# Lepton.net
KiCad netlist of a schematic drawn in EAGLE
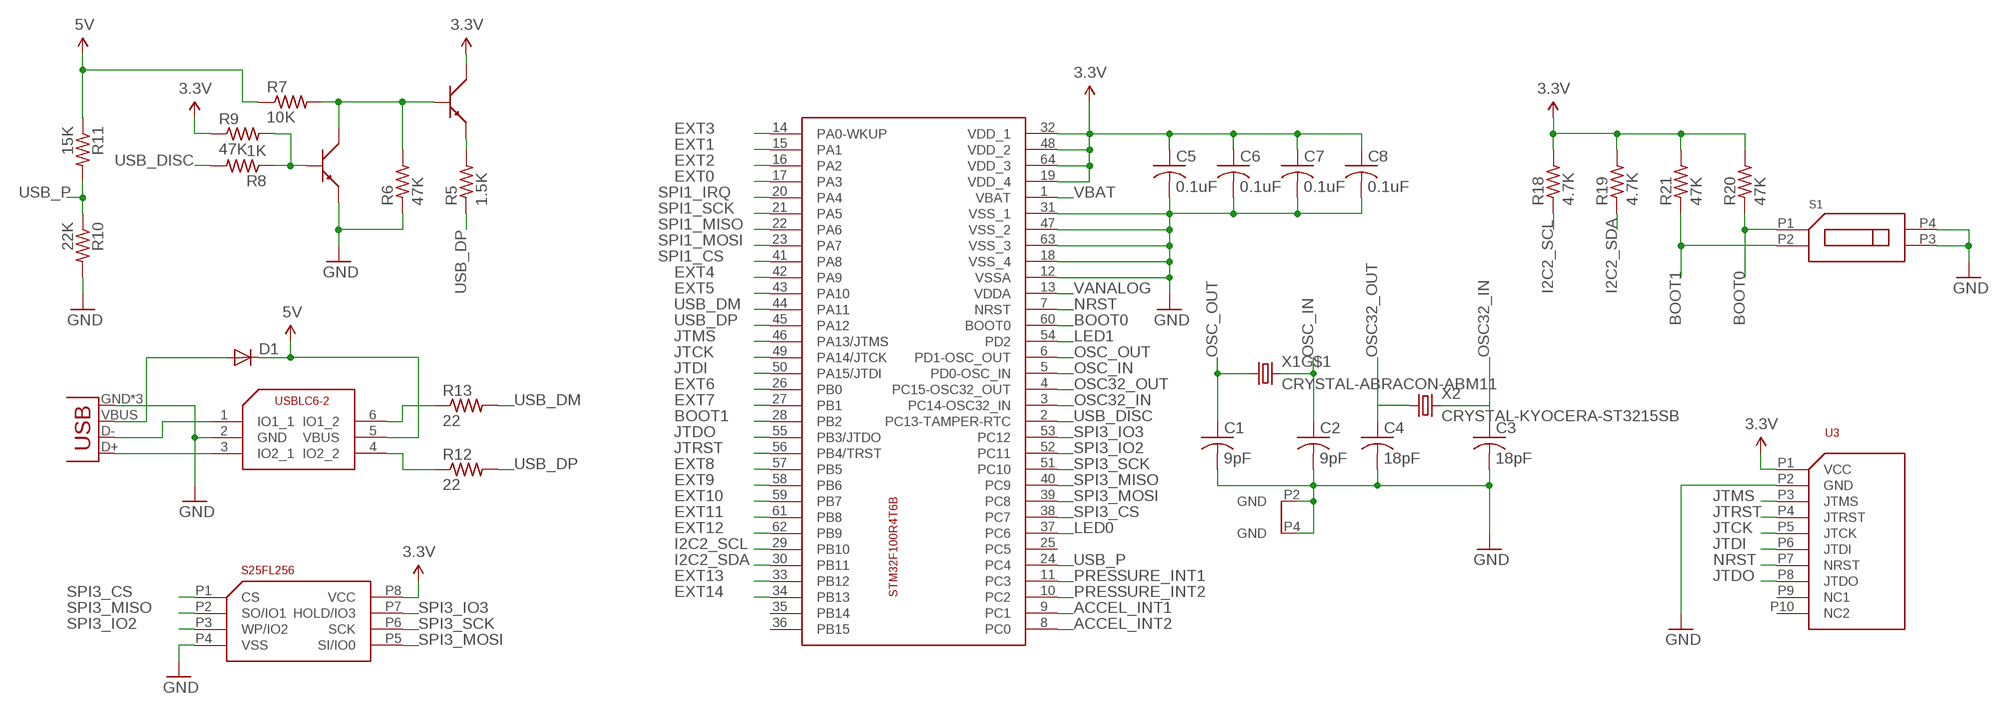
[diagram p0: schematic, sheet 1]
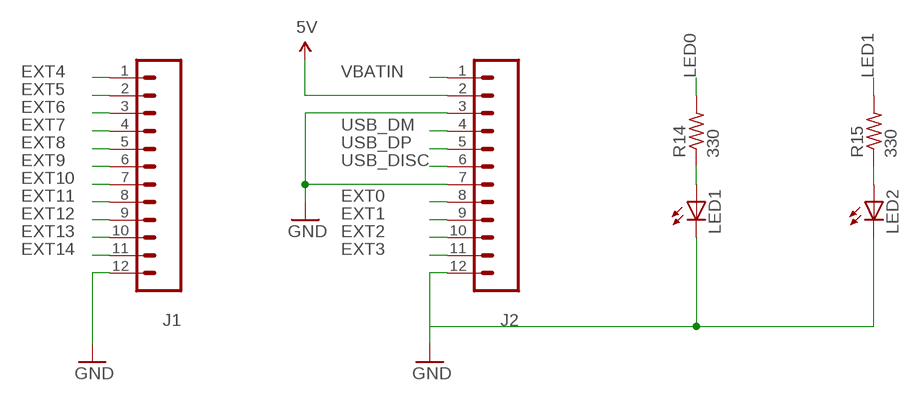
[diagram p1: schematic, sheet 2]
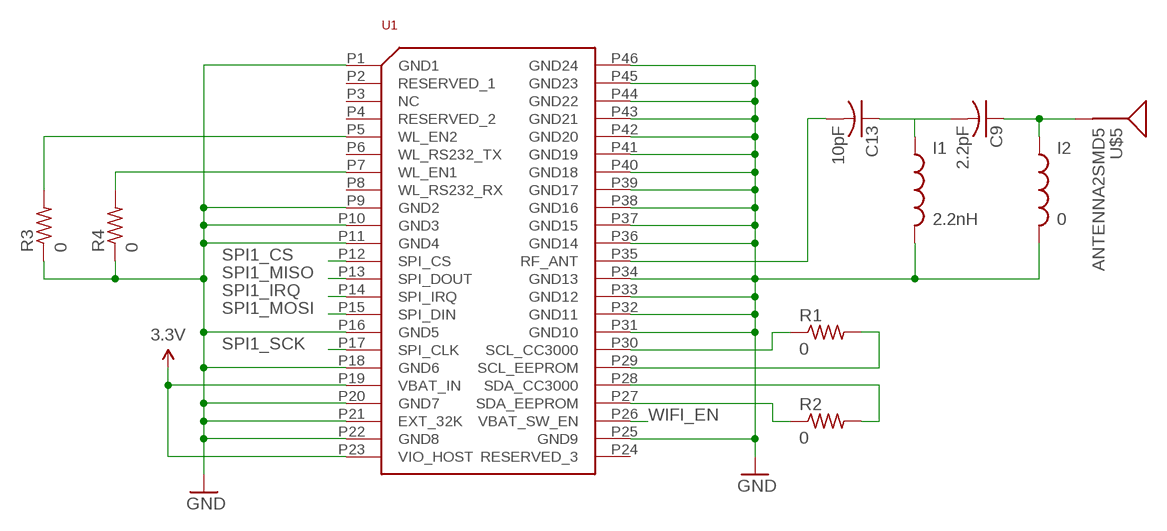
[diagram p2: schematic, sheet 3]
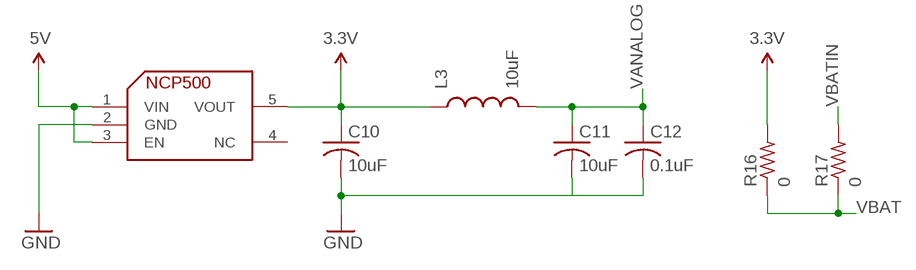
[diagram p3: schematic, sheet 4]
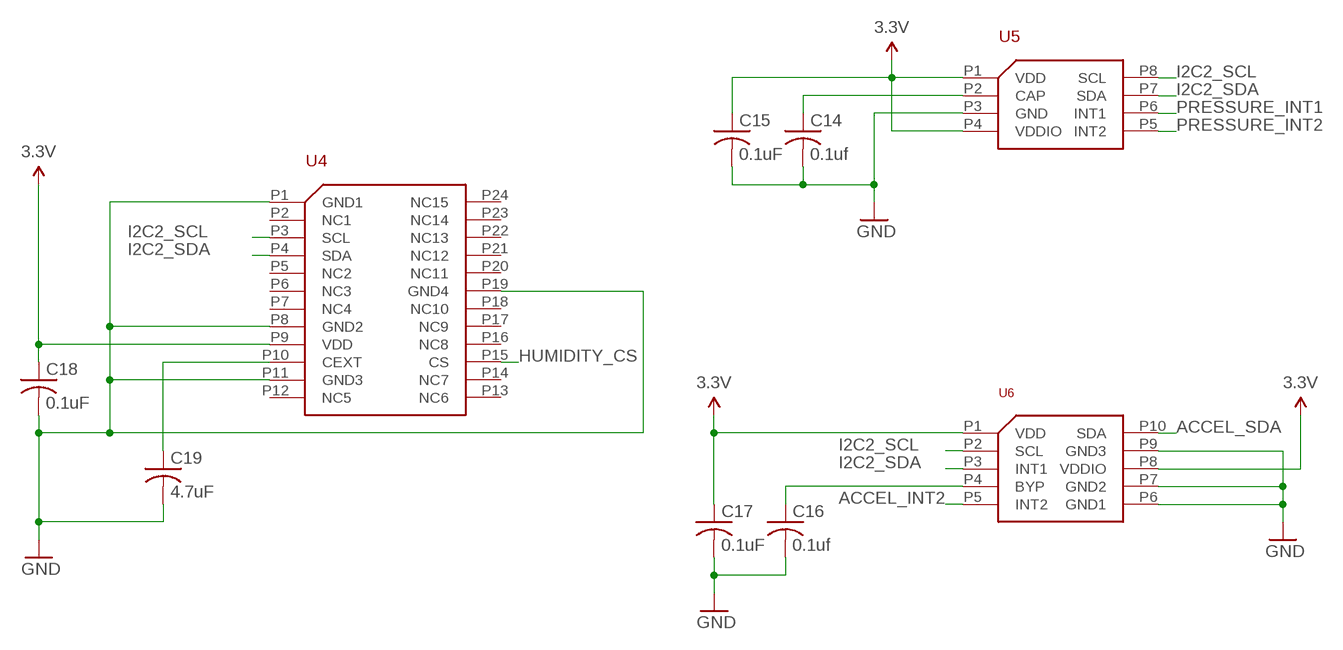
[diagram p4: schematic, sheet 5]

(export (version "E")
  (design (tool "Eeschema 10.0.6"))
  (components
    (comp (ref "C10")
      (value "10uF")
      (footprint "eagle-import:C0603")
      (libsource (lib "eagle-import") (part "C-USC0603"))
    )
    (comp (ref "C11")
      (value "10uF")
      (footprint "eagle-import:C0603")
      (libsource (lib "eagle-import") (part "C-USC0603"))
    )
    (comp (ref "C12")
      (value "0.1uF")
      (footprint "eagle-import:C0201")
      (libsource (lib "eagle-import") (part "C-USC0201"))
    )
    (comp (ref "L3")
      (value "10uF")
      (footprint "eagle-import:0603")
      (libsource (lib "eagle-import") (part "INDUCTOR0603"))
    )
    (comp (ref "R16")
      (value "0")
      (footprint "eagle-import:R0402")
      (libsource (lib "eagle-import") (part "R-US_R0402"))
    )
    (comp (ref "R17")
      (value "0")
      (footprint "eagle-import:R0402")
      (libsource (lib "eagle-import") (part "R-US_R0402"))
    )
    (comp (ref "U$7")
      (value "NCP500")
      (footprint "eagle-import:SOT23-5L")
      (libsource (lib "eagle-import") (part "NCP500"))
    )
    (comp (ref "C9")
      (value "2.2pF")
      (footprint "eagle-import:C0201")
      (libsource (lib "eagle-import") (part "C-USC0201"))
    )
    (comp (ref "C13")
      (value "10pF")
      (footprint "eagle-import:C0201")
      (libsource (lib "eagle-import") (part "C-USC0201"))
    )
    (comp (ref "I1")
      (value "2.2nH")
      (footprint "eagle-import:C0402")
      (libsource (lib "eagle-import") (part "INDUCTOR0402"))
    )
    (comp (ref "I2")
      (value "0")
      (footprint "eagle-import:C0402")
      (libsource (lib "eagle-import") (part "INDUCTOR0402"))
    )
    (comp (ref "R1")
      (value "0")
      (footprint "eagle-import:R0201")
      (libsource (lib "eagle-import") (part "R-US_R0201"))
    )
    (comp (ref "R2")
      (value "0")
      (footprint "eagle-import:R0201")
      (libsource (lib "eagle-import") (part "R-US_R0201"))
    )
    (comp (ref "R3")
      (value "0")
      (footprint "eagle-import:R0201")
      (libsource (lib "eagle-import") (part "R-US_R0201"))
    )
    (comp (ref "R4")
      (value "0")
      (footprint "eagle-import:R0201")
      (libsource (lib "eagle-import") (part "R-US_R0201"))
    )
    (comp (ref "U$5")
      (value "ANTENNA2SMD5")
      (footprint "eagle-import:ANTENNA-CHIP5")
      (libsource (lib "eagle-import") (part "ANTENNA2SMD5"))
    )
    (comp (ref "U1")
      (value "CC3000")
      (footprint "eagle-import:CC3000")
      (libsource (lib "eagle-import") (part "CC3000"))
    )
    (comp (ref "J1")
      (value "M12")
      (footprint "eagle-import:1X12")
      (libsource (lib "eagle-import") (part "M12"))
    )
    (comp (ref "J2")
      (value "M12")
      (footprint "eagle-import:1X12")
      (libsource (lib "eagle-import") (part "M12"))
    )
    (comp (ref "LED1")
      (value "LED0603")
      (footprint "eagle-import:LED-0603")
      (libsource (lib "eagle-import") (part "LED0603"))
    )
    (comp (ref "LED2")
      (value "LED0603")
      (footprint "eagle-import:LED-0603")
      (libsource (lib "eagle-import") (part "LED0603"))
    )
    (comp (ref "R14")
      (value "330")
      (footprint "eagle-import:R0201")
      (libsource (lib "eagle-import") (part "R-US_R0201"))
    )
    (comp (ref "R15")
      (value "330")
      (footprint "eagle-import:R0201")
      (libsource (lib "eagle-import") (part "R-US_R0201"))
    )
    (comp (ref "C14")
      (value "0.1uf")
      (footprint "eagle-import:C0201")
      (libsource (lib "eagle-import") (part "C-USC0201"))
    )
    (comp (ref "C15")
      (value "0.1uF")
      (footprint "eagle-import:C0201")
      (libsource (lib "eagle-import") (part "C-USC0201"))
    )
    (comp (ref "C16")
      (value "0.1uf")
      (footprint "eagle-import:C0201")
      (libsource (lib "eagle-import") (part "C-USC0201"))
    )
    (comp (ref "C17")
      (value "0.1uF")
      (footprint "eagle-import:C0201")
      (libsource (lib "eagle-import") (part "C-USC0201"))
    )
    (comp (ref "C18")
      (value "0.1uF")
      (footprint "eagle-import:C0201")
      (libsource (lib "eagle-import") (part "C-USC0201"))
    )
    (comp (ref "C19")
      (value "4.7uF")
      (footprint "eagle-import:C0402")
      (libsource (lib "eagle-import") (part "C-USC0402"))
    )
    (comp (ref "U4")
      (value "SILICONLABS-HUMIDITY-SI7005")
      (footprint "eagle-import:SILICONLABS-TQFN-24")
      (libsource (lib "eagle-import") (part "SILICONLABS-HUMIDITY-SI7005"))
    )
    (comp (ref "U5")
      (value "FREESCALE-PRESSURE-MPL3115A2")
      (footprint "eagle-import:UQFN-8L")
      (libsource (lib "eagle-import") (part "FREESCALE-PRESSURE-MPL3115A2"))
    )
    (comp (ref "U6")
      (value "MMA8653FC")
      (footprint "eagle-import:DFN-2X2-10")
      (libsource (lib "eagle-import") (part "MMA8653FC"))
    )
    (comp (ref "C1")
      (value "9pF")
      (footprint "eagle-import:C0201")
      (libsource (lib "eagle-import") (part "C-USC0201"))
    )
    (comp (ref "C2")
      (value "9pF")
      (footprint "eagle-import:C0201")
      (libsource (lib "eagle-import") (part "C-USC0201"))
    )
    (comp (ref "C3")
      (value "18pF")
      (footprint "eagle-import:C0201")
      (libsource (lib "eagle-import") (part "C-USC0201"))
    )
    (comp (ref "C4")
      (value "18pF")
      (footprint "eagle-import:C0201")
      (libsource (lib "eagle-import") (part "C-USC0201"))
    )
    (comp (ref "C5")
      (value "0.1uF")
      (footprint "eagle-import:C0201")
      (libsource (lib "eagle-import") (part "C-USC0201"))
    )
    (comp (ref "C6")
      (value "0.1uF")
      (footprint "eagle-import:C0201")
      (libsource (lib "eagle-import") (part "C-USC0201"))
    )
    (comp (ref "C7")
      (value "0.1uF")
      (footprint "eagle-import:C0201")
      (libsource (lib "eagle-import") (part "C-USC0201"))
    )
    (comp (ref "C8")
      (value "0.1uF")
      (footprint "eagle-import:C0201")
      (libsource (lib "eagle-import") (part "C-USC0201"))
    )
    (comp (ref "D1")
      (value "DIODE-MINIMELF")
      (footprint "eagle-import:MINIMELF")
      (libsource (lib "eagle-import") (part "DIODE-MINIMELF"))
    )
    (comp (ref "JP1")
      (value "USB-MICROB")
      (footprint "eagle-import:USB-MICROB")
      (libsource (lib "eagle-import") (part "USB-MICROB"))
    )
    (comp (ref "R5")
      (value "1.5K")
      (footprint "eagle-import:R0402")
      (libsource (lib "eagle-import") (part "R-US_R0402"))
    )
    (comp (ref "R6")
      (value "47K")
      (footprint "eagle-import:R0402")
      (libsource (lib "eagle-import") (part "R-US_R0402"))
    )
    (comp (ref "R7")
      (value "10K")
      (footprint "eagle-import:R0201")
      (libsource (lib "eagle-import") (part "R-US_R0201"))
    )
    (comp (ref "R8")
      (value "1K")
      (footprint "eagle-import:R0201")
      (libsource (lib "eagle-import") (part "R-US_R0201"))
    )
    (comp (ref "R9")
      (value "47K")
      (footprint "eagle-import:R0201")
      (libsource (lib "eagle-import") (part "R-US_R0201"))
    )
    (comp (ref "R10")
      (value "22K")
      (footprint "eagle-import:R0201")
      (libsource (lib "eagle-import") (part "R-US_R0201"))
    )
    (comp (ref "R11")
      (value "15K")
      (footprint "eagle-import:R0201")
      (libsource (lib "eagle-import") (part "R-US_R0201"))
    )
    (comp (ref "R12")
      (value "22")
      (footprint "eagle-import:R0201")
      (libsource (lib "eagle-import") (part "R-US_R0201"))
    )
    (comp (ref "R13")
      (value "22")
      (footprint "eagle-import:R0201")
      (libsource (lib "eagle-import") (part "R-US_R0201"))
    )
    (comp (ref "R18")
      (value "4.7K")
      (footprint "eagle-import:R0201")
      (libsource (lib "eagle-import") (part "R-US_R0201"))
    )
    (comp (ref "R19")
      (value "4.7K")
      (footprint "eagle-import:R0201")
      (libsource (lib "eagle-import") (part "R-US_R0201"))
    )
    (comp (ref "R20")
      (value "47K")
      (footprint "eagle-import:R0201")
      (libsource (lib "eagle-import") (part "R-US_R0201"))
    )
    (comp (ref "R21")
      (value "47K")
      (footprint "eagle-import:R0201")
      (libsource (lib "eagle-import") (part "R-US_R0201"))
    )
    (comp (ref "S1")
      (value "SWITCH-DIP-GDH-02")
      (footprint "eagle-import:SWITCH-DIP-GDH-02")
      (libsource (lib "eagle-import") (part "SWITCH-DIP-GDH-02"))
    )
    (comp (ref "U$1")
      (value "SPANSION-S25FL256")
      (footprint "eagle-import:SPANSION-WSON-8")
      (libsource (lib "eagle-import") (part "SPANSION-S25FL256"))
    )
    (comp (ref "U$2")
      (value "BIPOLAR-PMBT6428")
      (footprint "eagle-import:DUBLIB_SOT23")
      (libsource (lib "eagle-import") (part "BIPOLAR-PMBT6428"))
    )
    (comp (ref "U$3")
      (value "BIPOLAR-PMBT6428")
      (footprint "eagle-import:DUBLIB_SOT23")
      (libsource (lib "eagle-import") (part "BIPOLAR-PMBT6428"))
    )
    (comp (ref "U$4")
      (value "USBLC6-2")
      (footprint "eagle-import:SOT23-6L")
      (libsource (lib "eagle-import") (part "USBLC6-2"))
    )
    (comp (ref "U2")
      (value "STM32F100R4T6B")
      (footprint "eagle-import:S-PQFP64-G64")
      (libsource (lib "eagle-import") (part "STM32F100R4T6B"))
    )
    (comp (ref "U3")
      (value "STM32-JTAG-FFC")
      (footprint "eagle-import:FCI-FFC-10P-51281-1494")
      (libsource (lib "eagle-import") (part "STM32-JTAG-FFC"))
    )
    (comp (ref "X1")
      (value "CRYSTAL-ABRACON-ABM11")
      (footprint "eagle-import:ABM11")
      (libsource (lib "eagle-import") (part "CRYSTAL-ABRACON-ABM11"))
    )
    (comp (ref "X2")
      (value "CRYSTAL-KYOCERA-ST3215SB")
      (footprint "eagle-import:CRYSTAL-KYOCERA-ST3215SB")
      (libsource (lib "eagle-import") (part "CRYSTAL-KYOCERA-ST3215SB"))
    )
  )
  (nets
    (net (code "1") (name "3.3V") (class "Default")
      (node (ref "C10") (pin "1") (pinfunction "1_1") (pintype "passive"))
      (node (ref "C15") (pin "1") (pinfunction "1_1") (pintype "passive"))
      (node (ref "C17") (pin "1") (pinfunction "1_1") (pintype "passive"))
      (node (ref "C18") (pin "1") (pinfunction "1_1") (pintype "passive"))
      (node (ref "C5") (pin "1") (pinfunction "1_1") (pintype "passive"))
      (node (ref "C6") (pin "1") (pinfunction "1_1") (pintype "passive"))
      (node (ref "C7") (pin "1") (pinfunction "1_1") (pintype "passive"))
      (node (ref "C8") (pin "1") (pinfunction "1_1") (pintype "passive"))
      (node (ref "L3") (pin "1") (pinfunction "1_1") (pintype "passive"))
      (node (ref "R16") (pin "2") (pinfunction "2_2") (pintype "passive"))
      (node (ref "R18") (pin "2") (pinfunction "2_2") (pintype "passive"))
      (node (ref "R19") (pin "2") (pinfunction "2_2") (pintype "passive"))
      (node (ref "R20") (pin "2") (pinfunction "2_2") (pintype "passive"))
      (node (ref "R21") (pin "2") (pinfunction "2_2") (pintype "passive"))
      (node (ref "R9") (pin "1") (pinfunction "1_1") (pintype "passive"))
      (node (ref "U$1") (pin "P8") (pinfunction "VCC_P8") (pintype "bidirectional"))
      (node (ref "U$2") (pin "3") (pinfunction "3_3") (pintype "bidirectional"))
      (node (ref "U$7") (pin "5") (pinfunction "VOUT_5") (pintype "bidirectional"))
      (node (ref "U1") (pin "P19") (pinfunction "VBAT_IN_P19") (pintype "bidirectional"))
      (node (ref "U1") (pin "P23") (pinfunction "VIO_HOST_P23") (pintype "bidirectional"))
      (node (ref "U2") (pin "19") (pinfunction "VDD_4_19") (pintype "bidirectional"))
      (node (ref "U2") (pin "32") (pinfunction "VDD_1_32") (pintype "bidirectional"))
      (node (ref "U2") (pin "48") (pinfunction "VDD_2_48") (pintype "bidirectional"))
      (node (ref "U2") (pin "64") (pinfunction "VDD_3_64") (pintype "bidirectional"))
      (node (ref "U3") (pin "P1") (pinfunction "VCC_P1") (pintype "bidirectional"))
      (node (ref "U4") (pin "P9") (pinfunction "VDD_P9") (pintype "bidirectional"))
      (node (ref "U5") (pin "P1") (pinfunction "VDD_P1") (pintype "bidirectional"))
      (node (ref "U5") (pin "P4") (pinfunction "VDDIO_P4") (pintype "bidirectional"))
      (node (ref "U6") (pin "P1") (pinfunction "VDD_P1") (pintype "bidirectional"))
      (node (ref "U6") (pin "P8") (pinfunction "VDDIO_P8") (pintype "bidirectional"))
    )
    (net (code "2") (name "5V") (class "Default")
      (node (ref "D1") (pin "C") (pinfunction "C_C") (pintype "passive"))
      (node (ref "J2") (pin "2") (pinfunction "2_2") (pintype "passive"))
      (node (ref "R11") (pin "1") (pinfunction "1_1") (pintype "passive"))
      (node (ref "R7") (pin "1") (pinfunction "1_1") (pintype "passive"))
      (node (ref "U$4") (pin "5") (pinfunction "VBUS_5") (pintype "bidirectional"))
      (node (ref "U$7") (pin "1") (pinfunction "VIN_1") (pintype "bidirectional"))
      (node (ref "U$7") (pin "3") (pinfunction "EN_3") (pintype "bidirectional"))
    )
    (net (code "3") (name "ACCEL_INT1") (class "Default")
      (node (ref "U2") (pin "9") (pinfunction "PC1_9") (pintype "bidirectional"))
    )
    (net (code "4") (name "ACCEL_INT2") (class "Default")
      (node (ref "U2") (pin "8") (pinfunction "PC0_8") (pintype "bidirectional"))
      (node (ref "U6") (pin "P5") (pinfunction "INT2_P5") (pintype "bidirectional"))
    )
    (net (code "5") (name "ACCEL_SDA") (class "Default")
      (node (ref "U6") (pin "P10") (pinfunction "SDA_P10") (pintype "bidirectional"))
    )
    (net (code "6") (name "BOOT0") (class "Default")
      (node (ref "R20") (pin "1") (pinfunction "1_1") (pintype "passive"))
      (node (ref "S1") (pin "P1") (pinfunction "SW0_0_P1") (pintype "bidirectional"))
      (node (ref "U2") (pin "60") (pinfunction "BOOT0_60") (pintype "bidirectional"))
    )
    (net (code "7") (name "BOOT1") (class "Default")
      (node (ref "R21") (pin "1") (pinfunction "1_1") (pintype "passive"))
      (node (ref "S1") (pin "P2") (pinfunction "SW1_0_P2") (pintype "bidirectional"))
      (node (ref "U2") (pin "28") (pinfunction "PB2_28") (pintype "bidirectional"))
    )
    (net (code "8") (name "EXT0") (class "Default")
      (node (ref "J2") (pin "8") (pinfunction "8_8") (pintype "passive"))
      (node (ref "U2") (pin "17") (pinfunction "PA3_17") (pintype "bidirectional"))
    )
    (net (code "9") (name "EXT1") (class "Default")
      (node (ref "J2") (pin "9") (pinfunction "9_9") (pintype "passive"))
      (node (ref "U2") (pin "15") (pinfunction "PA1_15") (pintype "bidirectional"))
    )
    (net (code "10") (name "EXT2") (class "Default")
      (node (ref "J2") (pin "10") (pinfunction "10_10") (pintype "passive"))
      (node (ref "U2") (pin "16") (pinfunction "PA2_16") (pintype "bidirectional"))
    )
    (net (code "11") (name "EXT3") (class "Default")
      (node (ref "J2") (pin "11") (pinfunction "11_11") (pintype "passive"))
      (node (ref "U2") (pin "14") (pinfunction "PA0-WKUP_14") (pintype "bidirectional"))
    )
    (net (code "12") (name "EXT4") (class "Default")
      (node (ref "J1") (pin "1") (pinfunction "1_1") (pintype "passive"))
      (node (ref "U2") (pin "42") (pinfunction "PA9_42") (pintype "bidirectional"))
    )
    (net (code "13") (name "EXT5") (class "Default")
      (node (ref "J1") (pin "2") (pinfunction "2_2") (pintype "passive"))
      (node (ref "U2") (pin "43") (pinfunction "PA10_43") (pintype "bidirectional"))
    )
    (net (code "14") (name "EXT6") (class "Default")
      (node (ref "J1") (pin "3") (pinfunction "3_3") (pintype "passive"))
      (node (ref "U2") (pin "26") (pinfunction "PB0_26") (pintype "bidirectional"))
    )
    (net (code "15") (name "EXT7") (class "Default")
      (node (ref "J1") (pin "4") (pinfunction "4_4") (pintype "passive"))
      (node (ref "U2") (pin "27") (pinfunction "PB1_27") (pintype "bidirectional"))
    )
    (net (code "16") (name "EXT8") (class "Default")
      (node (ref "J1") (pin "5") (pinfunction "5_5") (pintype "passive"))
      (node (ref "U2") (pin "57") (pinfunction "PB5_57") (pintype "bidirectional"))
    )
    (net (code "17") (name "EXT9") (class "Default")
      (node (ref "J1") (pin "6") (pinfunction "6_6") (pintype "passive"))
      (node (ref "U2") (pin "58") (pinfunction "PB6_58") (pintype "bidirectional"))
    )
    (net (code "18") (name "EXT10") (class "Default")
      (node (ref "J1") (pin "7") (pinfunction "7_7") (pintype "passive"))
      (node (ref "U2") (pin "59") (pinfunction "PB7_59") (pintype "bidirectional"))
    )
    (net (code "19") (name "EXT11") (class "Default")
      (node (ref "J1") (pin "8") (pinfunction "8_8") (pintype "passive"))
      (node (ref "U2") (pin "61") (pinfunction "PB8_61") (pintype "bidirectional"))
    )
    (net (code "20") (name "EXT12") (class "Default")
      (node (ref "J1") (pin "9") (pinfunction "9_9") (pintype "passive"))
      (node (ref "U2") (pin "62") (pinfunction "PB9_62") (pintype "bidirectional"))
    )
    (net (code "21") (name "EXT13") (class "Default")
      (node (ref "J1") (pin "10") (pinfunction "10_10") (pintype "passive"))
      (node (ref "U2") (pin "33") (pinfunction "PB12_33") (pintype "bidirectional"))
    )
    (net (code "22") (name "EXT14") (class "Default")
      (node (ref "J1") (pin "11") (pinfunction "11_11") (pintype "passive"))
      (node (ref "U2") (pin "34") (pinfunction "PB13_34") (pintype "bidirectional"))
    )
    (net (code "23") (name "GND") (class "Default")
      (node (ref "C1") (pin "2") (pinfunction "2_2") (pintype "passive"))
      (node (ref "C10") (pin "2") (pinfunction "2_2") (pintype "passive"))
      (node (ref "C11") (pin "2") (pinfunction "2_2") (pintype "passive"))
      (node (ref "C12") (pin "2") (pinfunction "2_2") (pintype "passive"))
      (node (ref "C14") (pin "2") (pinfunction "2_2") (pintype "passive"))
      (node (ref "C15") (pin "2") (pinfunction "2_2") (pintype "passive"))
      (node (ref "C16") (pin "2") (pinfunction "2_2") (pintype "passive"))
      (node (ref "C17") (pin "2") (pinfunction "2_2") (pintype "passive"))
      (node (ref "C18") (pin "2") (pinfunction "2_2") (pintype "passive"))
      (node (ref "C19") (pin "2") (pinfunction "2_2") (pintype "passive"))
      (node (ref "C2") (pin "2") (pinfunction "2_2") (pintype "passive"))
      (node (ref "C3") (pin "2") (pinfunction "2_2") (pintype "passive"))
      (node (ref "C4") (pin "2") (pinfunction "2_2") (pintype "passive"))
      (node (ref "C5") (pin "2") (pinfunction "2_2") (pintype "passive"))
      (node (ref "C6") (pin "2") (pinfunction "2_2") (pintype "passive"))
      (node (ref "C7") (pin "2") (pinfunction "2_2") (pintype "passive"))
      (node (ref "C8") (pin "2") (pinfunction "2_2") (pintype "passive"))
      (node (ref "I1") (pin "2") (pinfunction "2_2") (pintype "passive"))
      (node (ref "I2") (pin "2") (pinfunction "2_2") (pintype "passive"))
      (node (ref "J1") (pin "12") (pinfunction "12_12") (pintype "passive"))
      (node (ref "J2") (pin "12") (pinfunction "12_12") (pintype "passive"))
      (node (ref "J2") (pin "3") (pinfunction "3_3") (pintype "passive"))
      (node (ref "J2") (pin "7") (pinfunction "7_7") (pintype "passive"))
      (node (ref "JP1") (pin "GND") (pinfunction "GND_GND") (pintype "bidirectional"))
      (node (ref "JP1") (pin "MT1") (pinfunction "GND_MT1") (pintype "bidirectional"))
      (node (ref "JP1") (pin "MT2") (pinfunction "GND_MT2") (pintype "bidirectional"))
      (node (ref "LED1") (pin "C") (pinfunction "C_C") (pintype "passive"))
      (node (ref "LED2") (pin "C") (pinfunction "C_C") (pintype "passive"))
      (node (ref "R10") (pin "2") (pinfunction "2_2") (pintype "passive"))
      (node (ref "R3") (pin "1") (pinfunction "1_1") (pintype "passive"))
      (node (ref "R4") (pin "1") (pinfunction "1_1") (pintype "passive"))
      (node (ref "R6") (pin "1") (pinfunction "1_1") (pintype "passive"))
      (node (ref "S1") (pin "P3") (pinfunction "SW1_1_P3") (pintype "bidirectional"))
      (node (ref "S1") (pin "P4") (pinfunction "SW0_1_P4") (pintype "bidirectional"))
      (node (ref "U$1") (pin "P4") (pinfunction "VSS_P4") (pintype "bidirectional"))
      (node (ref "U$3") (pin "2") (pinfunction "2_2") (pintype "bidirectional"))
      (node (ref "U$4") (pin "2") (pinfunction "GND_2") (pintype "bidirectional"))
      (node (ref "U$7") (pin "2") (pinfunction "GND_2") (pintype "bidirectional"))
      (node (ref "U1") (pin "P1") (pinfunction "GND1_P1") (pintype "bidirectional"))
      (node (ref "U1") (pin "P10") (pinfunction "GND3_P10") (pintype "bidirectional"))
      (node (ref "U1") (pin "P11") (pinfunction "GND4_P11") (pintype "bidirectional"))
      (node (ref "U1") (pin "P16") (pinfunction "GND5_P16") (pintype "bidirectional"))
      (node (ref "U1") (pin "P18") (pinfunction "GND6_P18") (pintype "bidirectional"))
      (node (ref "U1") (pin "P20") (pinfunction "GND7_P20") (pintype "bidirectional"))
      (node (ref "U1") (pin "P21") (pinfunction "EXT_32K_P21") (pintype "bidirectional"))
      (node (ref "U1") (pin "P22") (pinfunction "GND8_P22") (pintype "bidirectional"))
      (node (ref "U1") (pin "P25") (pinfunction "GND9_P25") (pintype "bidirectional"))
      (node (ref "U1") (pin "P31") (pinfunction "GND10_P31") (pintype "bidirectional"))
      (node (ref "U1") (pin "P32") (pinfunction "GND11_P32") (pintype "bidirectional"))
      (node (ref "U1") (pin "P33") (pinfunction "GND12_P33") (pintype "bidirectional"))
      (node (ref "U1") (pin "P34") (pinfunction "GND13_P34") (pintype "bidirectional"))
      (node (ref "U1") (pin "P36") (pinfunction "GND14_P36") (pintype "bidirectional"))
      (node (ref "U1") (pin "P37") (pinfunction "GND15_P37") (pintype "bidirectional"))
      (node (ref "U1") (pin "P38") (pinfunction "GND16_P38") (pintype "bidirectional"))
      (node (ref "U1") (pin "P39") (pinfunction "GND17_P39") (pintype "bidirectional"))
      (node (ref "U1") (pin "P40") (pinfunction "GND18_P40") (pintype "bidirectional"))
      (node (ref "U1") (pin "P41") (pinfunction "GND19_P41") (pintype "bidirectional"))
      (node (ref "U1") (pin "P42") (pinfunction "GND20_P42") (pintype "bidirectional"))
      (node (ref "U1") (pin "P43") (pinfunction "GND21_P43") (pintype "bidirectional"))
      (node (ref "U1") (pin "P44") (pinfunction "GND22_P44") (pintype "bidirectional"))
      (node (ref "U1") (pin "P45") (pinfunction "GND23_P45") (pintype "bidirectional"))
      (node (ref "U1") (pin "P46") (pinfunction "GND24_P46") (pintype "bidirectional"))
      (node (ref "U1") (pin "P9") (pinfunction "GND2_P9") (pintype "bidirectional"))
      (node (ref "U2") (pin "12") (pinfunction "VSSA_12") (pintype "bidirectional"))
      (node (ref "U2") (pin "18") (pinfunction "VSS_4_18") (pintype "bidirectional"))
      (node (ref "U2") (pin "31") (pinfunction "VSS_1_31") (pintype "bidirectional"))
      (node (ref "U2") (pin "47") (pinfunction "VSS_2_47") (pintype "bidirectional"))
      (node (ref "U2") (pin "63") (pinfunction "VSS_3_63") (pintype "bidirectional"))
      (node (ref "U3") (pin "P2") (pinfunction "GND_P2") (pintype "bidirectional"))
      (node (ref "U4") (pin "P1") (pinfunction "GND1_P1") (pintype "bidirectional"))
      (node (ref "U4") (pin "P11") (pinfunction "GND3_P11") (pintype "bidirectional"))
      (node (ref "U4") (pin "P19") (pinfunction "GND4_P19") (pintype "bidirectional"))
      (node (ref "U4") (pin "P8") (pinfunction "GND2_P8") (pintype "bidirectional"))
      (node (ref "U5") (pin "P3") (pinfunction "GND_P3") (pintype "bidirectional"))
      (node (ref "U6") (pin "P6") (pinfunction "GND1_P6") (pintype "bidirectional"))
      (node (ref "U6") (pin "P7") (pinfunction "GND2_P7") (pintype "bidirectional"))
      (node (ref "U6") (pin "P9") (pinfunction "GND3_P9") (pintype "bidirectional"))
      (node (ref "X1") (pin "P2") (pinfunction "GND_P2") (pintype "power_in"))
      (node (ref "X1") (pin "P4") (pinfunction "GND_P4") (pintype "power_in"))
    )
    (net (code "24") (name "HUMIDITY_CS") (class "Default")
      (node (ref "U4") (pin "P15") (pinfunction "CS_P15") (pintype "bidirectional"))
    )
    (net (code "25") (name "I2C2_SCL") (class "Default")
      (node (ref "R18") (pin "1") (pinfunction "1_1") (pintype "passive"))
      (node (ref "U2") (pin "29") (pinfunction "PB10_29") (pintype "bidirectional"))
      (node (ref "U4") (pin "P3") (pinfunction "SCL_P3") (pintype "bidirectional"))
      (node (ref "U5") (pin "P8") (pinfunction "SCL_P8") (pintype "bidirectional"))
      (node (ref "U6") (pin "P2") (pinfunction "SCL_P2") (pintype "bidirectional"))
    )
    (net (code "26") (name "I2C2_SDA") (class "Default")
      (node (ref "R19") (pin "1") (pinfunction "1_1") (pintype "passive"))
      (node (ref "U2") (pin "30") (pinfunction "PB11_30") (pintype "bidirectional"))
      (node (ref "U4") (pin "P4") (pinfunction "SDA_P4") (pintype "bidirectional"))
      (node (ref "U5") (pin "P7") (pinfunction "SDA_P7") (pintype "bidirectional"))
      (node (ref "U6") (pin "P3") (pinfunction "INT1_P3") (pintype "bidirectional"))
    )
    (net (code "27") (name "JTCK") (class "Default")
      (node (ref "U2") (pin "49") (pinfunction "PA14/JTCK_49") (pintype "bidirectional"))
      (node (ref "U3") (pin "P5") (pinfunction "JTCK_P5") (pintype "bidirectional"))
    )
    (net (code "28") (name "JTDI") (class "Default")
      (node (ref "U2") (pin "50") (pinfunction "PA15/JTDI_50") (pintype "bidirectional"))
      (node (ref "U3") (pin "P6") (pinfunction "JTDI_P6") (pintype "bidirectional"))
    )
    (net (code "29") (name "JTDO") (class "Default")
      (node (ref "U2") (pin "55") (pinfunction "PB3/JTDO_55") (pintype "bidirectional"))
      (node (ref "U3") (pin "P8") (pinfunction "JTDO_P8") (pintype "bidirectional"))
    )
    (net (code "30") (name "JTMS") (class "Default")
      (node (ref "U2") (pin "46") (pinfunction "PA13/JTMS_46") (pintype "bidirectional"))
      (node (ref "U3") (pin "P3") (pinfunction "JTMS_P3") (pintype "bidirectional"))
    )
    (net (code "31") (name "JTRST") (class "Default")
      (node (ref "U2") (pin "56") (pinfunction "PB4/TRST_56") (pintype "bidirectional"))
      (node (ref "U3") (pin "P4") (pinfunction "JTRST_P4") (pintype "bidirectional"))
    )
    (net (code "32") (name "LED0") (class "Default")
      (node (ref "R14") (pin "2") (pinfunction "2_2") (pintype "passive"))
      (node (ref "U2") (pin "37") (pinfunction "PC6_37") (pintype "bidirectional"))
    )
    (net (code "33") (name "LED1") (class "Default")
      (node (ref "R15") (pin "2") (pinfunction "2_2") (pintype "passive"))
      (node (ref "U2") (pin "54") (pinfunction "PD2_54") (pintype "bidirectional"))
    )
    (net (code "34") (name "NRST") (class "Default")
      (node (ref "U2") (pin "7") (pinfunction "NRST_7") (pintype "bidirectional"))
      (node (ref "U3") (pin "P7") (pinfunction "NRST_P7") (pintype "bidirectional"))
    )
    (net (code "35") (name "Net-(C13-Pad1)") (class "Default")
      (node (ref "C13") (pin "1") (pinfunction "1_1") (pintype "passive"))
      (node (ref "C9") (pin "2") (pinfunction "2_2") (pintype "passive"))
      (node (ref "I1") (pin "1") (pinfunction "1_1") (pintype "passive"))
    )
    (net (code "36") (name "Net-(D1-PadA)") (class "Default")
      (node (ref "D1") (pin "A") (pinfunction "A_A") (pintype "passive"))
      (node (ref "JP1") (pin "VBUS") (pinfunction "VBUS_VBUS") (pintype "bidirectional"))
    )
    (net (code "37") (name "Net-(LED1-PadA)") (class "Default")
      (node (ref "LED1") (pin "A") (pinfunction "A_A") (pintype "passive"))
      (node (ref "R14") (pin "1") (pinfunction "1_1") (pintype "passive"))
    )
    (net (code "38") (name "Net-(LED2-PadA)") (class "Default")
      (node (ref "LED2") (pin "A") (pinfunction "A_A") (pintype "passive"))
      (node (ref "R15") (pin "1") (pinfunction "1_1") (pintype "passive"))
    )
    (net (code "39") (name "Net-(R5-Pad2)") (class "Default")
      (node (ref "R5") (pin "2") (pinfunction "2_2") (pintype "passive"))
      (node (ref "U$2") (pin "2") (pinfunction "2_2") (pintype "bidirectional"))
    )
    (net (code "40") (name "Net-(R6-Pad2)") (class "Default")
      (node (ref "R6") (pin "2") (pinfunction "2_2") (pintype "passive"))
      (node (ref "R7") (pin "2") (pinfunction "2_2") (pintype "passive"))
      (node (ref "U$2") (pin "1") (pinfunction "1_1") (pintype "bidirectional"))
      (node (ref "U$3") (pin "3") (pinfunction "3_3") (pintype "bidirectional"))
    )
    (net (code "41") (name "Net-(R8-Pad1)") (class "Default")
      (node (ref "R8") (pin "1") (pinfunction "1_1") (pintype "passive"))
      (node (ref "R9") (pin "2") (pinfunction "2_2") (pintype "passive"))
      (node (ref "U$3") (pin "1") (pinfunction "1_1") (pintype "bidirectional"))
    )
    (net (code "42") (name "Net-(U$4-IO1_1)") (class "Default")
      (node (ref "JP1") (pin "D-") (pinfunction "D-_D-") (pintype "bidirectional"))
      (node (ref "U$4") (pin "1") (pinfunction "IO1_1_1") (pintype "bidirectional"))
    )
    (net (code "43") (name "Net-(U$4-IO1_2)") (class "Default")
      (node (ref "R13") (pin "1") (pinfunction "1_1") (pintype "passive"))
      (node (ref "U$4") (pin "6") (pinfunction "IO1_2_6") (pintype "bidirectional"))
    )
    (net (code "44") (name "Net-(U$4-IO2_1)") (class "Default")
      (node (ref "JP1") (pin "D+") (pinfunction "D+_D+") (pintype "bidirectional"))
      (node (ref "U$4") (pin "3") (pinfunction "IO2_1_3") (pintype "bidirectional"))
    )
    (net (code "45") (name "Net-(U$4-IO2_2)") (class "Default")
      (node (ref "R12") (pin "1") (pinfunction "1_1") (pintype "passive"))
      (node (ref "U$4") (pin "4") (pinfunction "IO2_2_4") (pintype "bidirectional"))
    )
    (net (code "46") (name "Net-(U$5-SIGNAL)") (class "Default")
      (node (ref "C9") (pin "1") (pinfunction "1_1") (pintype "passive"))
      (node (ref "I2") (pin "1") (pinfunction "1_1") (pintype "passive"))
      (node (ref "U$5") (pin "FEED") (pinfunction "SIGNAL_FEED") (pintype "bidirectional"))
    )
    (net (code "47") (name "Net-(U1-RF_ANT)") (class "Default")
      (node (ref "C13") (pin "2") (pinfunction "2_2") (pintype "passive"))
      (node (ref "U1") (pin "P35") (pinfunction "RF_ANT_P35") (pintype "bidirectional"))
    )
    (net (code "48") (name "Net-(U1-SCL_CC3000)") (class "Default")
      (node (ref "R1") (pin "1") (pinfunction "1_1") (pintype "passive"))
      (node (ref "U1") (pin "P30") (pinfunction "SCL_CC3000_P30") (pintype "bidirectional"))
    )
    (net (code "49") (name "Net-(U1-SCL_EEPROM)") (class "Default")
      (node (ref "R1") (pin "2") (pinfunction "2_2") (pintype "passive"))
      (node (ref "U1") (pin "P29") (pinfunction "SCL_EEPROM_P29") (pintype "bidirectional"))
    )
    (net (code "50") (name "Net-(U1-SDA_CC3000)") (class "Default")
      (node (ref "R2") (pin "2") (pinfunction "2_2") (pintype "passive"))
      (node (ref "U1") (pin "P28") (pinfunction "SDA_CC3000_P28") (pintype "bidirectional"))
    )
    (net (code "51") (name "Net-(U1-SDA_EEPROM)") (class "Default")
      (node (ref "R2") (pin "1") (pinfunction "1_1") (pintype "passive"))
      (node (ref "U1") (pin "P27") (pinfunction "SDA_EEPROM_P27") (pintype "bidirectional"))
    )
    (net (code "52") (name "Net-(U1-WL_EN1)") (class "Default")
      (node (ref "R4") (pin "2") (pinfunction "2_2") (pintype "passive"))
      (node (ref "U1") (pin "P7") (pinfunction "WL_EN1_P7") (pintype "bidirectional"))
    )
    (net (code "53") (name "Net-(U1-WL_EN2)") (class "Default")
      (node (ref "R3") (pin "2") (pinfunction "2_2") (pintype "passive"))
      (node (ref "U1") (pin "P5") (pinfunction "WL_EN2_P5") (pintype "bidirectional"))
    )
    (net (code "54") (name "Net-(U4-CEXT)") (class "Default")
      (node (ref "C19") (pin "1") (pinfunction "1_1") (pintype "passive"))
      (node (ref "U4") (pin "P10") (pinfunction "CEXT_P10") (pintype "bidirectional"))
    )
    (net (code "55") (name "Net-(U5-CAP)") (class "Default")
      (node (ref "C14") (pin "1") (pinfunction "1_1") (pintype "passive"))
      (node (ref "U5") (pin "P2") (pinfunction "CAP_P2") (pintype "bidirectional"))
    )
    (net (code "56") (name "Net-(U6-BYP)") (class "Default")
      (node (ref "C16") (pin "1") (pinfunction "1_1") (pintype "passive"))
      (node (ref "U6") (pin "P4") (pinfunction "BYP_P4") (pintype "bidirectional"))
    )
    (net (code "57") (name "OSC32_IN") (class "Default")
      (node (ref "C3") (pin "1") (pinfunction "1_1") (pintype "passive"))
      (node (ref "U2") (pin "3") (pinfunction "PC14-OSC32_IN_3") (pintype "bidirectional"))
      (node (ref "X2") (pin "P2") (pinfunction "2_P2") (pintype "passive"))
    )
    (net (code "58") (name "OSC32_OUT") (class "Default")
      (node (ref "C4") (pin "1") (pinfunction "1_1") (pintype "passive"))
      (node (ref "U2") (pin "4") (pinfunction "PC15-OSC32_OUT_4") (pintype "bidirectional"))
      (node (ref "X2") (pin "P1") (pinfunction "1_P1") (pintype "passive"))
    )
    (net (code "59") (name "OSC_IN") (class "Default")
      (node (ref "C2") (pin "1") (pinfunction "1_1") (pintype "passive"))
      (node (ref "U2") (pin "5") (pinfunction "PD0-OSC_IN_5") (pintype "bidirectional"))
      (node (ref "X1") (pin "P3") (pinfunction "2_P3") (pintype "passive"))
    )
    (net (code "60") (name "OSC_OUT") (class "Default")
      (node (ref "C1") (pin "1") (pinfunction "1_1") (pintype "passive"))
      (node (ref "U2") (pin "6") (pinfunction "PD1-OSC_OUT_6") (pintype "bidirectional"))
      (node (ref "X1") (pin "P1") (pinfunction "1_P1") (pintype "passive"))
    )
    (net (code "61") (name "PRESSURE_INT1") (class "Default")
      (node (ref "U2") (pin "11") (pinfunction "PC3_11") (pintype "bidirectional"))
      (node (ref "U5") (pin "P6") (pinfunction "INT1_P6") (pintype "bidirectional"))
    )
    (net (code "62") (name "PRESSURE_INT2") (class "Default")
      (node (ref "U2") (pin "10") (pinfunction "PC2_10") (pintype "bidirectional"))
      (node (ref "U5") (pin "P5") (pinfunction "INT2_P5") (pintype "bidirectional"))
    )
    (net (code "63") (name "SPI1_CS") (class "Default")
      (node (ref "U1") (pin "P12") (pinfunction "SPI_CS_P12") (pintype "bidirectional"))
      (node (ref "U2") (pin "41") (pinfunction "PA8_41") (pintype "bidirectional"))
    )
    (net (code "64") (name "SPI1_IRQ") (class "Default")
      (node (ref "U1") (pin "P14") (pinfunction "SPI_IRQ_P14") (pintype "bidirectional"))
      (node (ref "U2") (pin "20") (pinfunction "PA4_20") (pintype "bidirectional"))
    )
    (net (code "65") (name "SPI1_MISO") (class "Default")
      (node (ref "U1") (pin "P13") (pinfunction "SPI_DOUT_P13") (pintype "bidirectional"))
      (node (ref "U2") (pin "22") (pinfunction "PA6_22") (pintype "bidirectional"))
    )
    (net (code "66") (name "SPI1_MOSI") (class "Default")
      (node (ref "U1") (pin "P15") (pinfunction "SPI_DIN_P15") (pintype "bidirectional"))
      (node (ref "U2") (pin "23") (pinfunction "PA7_23") (pintype "bidirectional"))
    )
    (net (code "67") (name "SPI1_SCK") (class "Default")
      (node (ref "U1") (pin "P17") (pinfunction "SPI_CLK_P17") (pintype "bidirectional"))
      (node (ref "U2") (pin "21") (pinfunction "PA5_21") (pintype "bidirectional"))
    )
    (net (code "68") (name "SPI3_CS") (class "Default")
      (node (ref "U$1") (pin "P1") (pinfunction "CS_P1") (pintype "bidirectional"))
      (node (ref "U2") (pin "38") (pinfunction "PC7_38") (pintype "bidirectional"))
    )
    (net (code "69") (name "SPI3_IO2") (class "Default")
      (node (ref "U$1") (pin "P3") (pinfunction "WP/IO2_P3") (pintype "bidirectional"))
      (node (ref "U2") (pin "52") (pinfunction "PC11_52") (pintype "bidirectional"))
    )
    (net (code "70") (name "SPI3_IO3") (class "Default")
      (node (ref "U$1") (pin "P7") (pinfunction "HOLD/IO3_P7") (pintype "bidirectional"))
      (node (ref "U2") (pin "53") (pinfunction "PC12_53") (pintype "bidirectional"))
    )
    (net (code "71") (name "SPI3_MISO") (class "Default")
      (node (ref "U$1") (pin "P2") (pinfunction "SO/IO1_P2") (pintype "bidirectional"))
      (node (ref "U2") (pin "40") (pinfunction "PC9_40") (pintype "bidirectional"))
    )
    (net (code "72") (name "SPI3_MOSI") (class "Default")
      (node (ref "U$1") (pin "P5") (pinfunction "SI/IO0_P5") (pintype "bidirectional"))
      (node (ref "U2") (pin "39") (pinfunction "PC8_39") (pintype "bidirectional"))
    )
    (net (code "73") (name "SPI3_SCK") (class "Default")
      (node (ref "U$1") (pin "P6") (pinfunction "SCK_P6") (pintype "bidirectional"))
      (node (ref "U2") (pin "51") (pinfunction "PC10_51") (pintype "bidirectional"))
    )
    (net (code "74") (name "USB_DISC") (class "Default")
      (node (ref "J2") (pin "6") (pinfunction "6_6") (pintype "passive"))
      (node (ref "R8") (pin "2") (pinfunction "2_2") (pintype "passive"))
      (node (ref "U2") (pin "2") (pinfunction "PC13-TAMPER-RTC_2") (pintype "bidirectional"))
    )
    (net (code "75") (name "USB_DM") (class "Default")
      (node (ref "J2") (pin "4") (pinfunction "4_4") (pintype "passive"))
      (node (ref "R13") (pin "2") (pinfunction "2_2") (pintype "passive"))
      (node (ref "U2") (pin "44") (pinfunction "PA11_44") (pintype "bidirectional"))
    )
    (net (code "76") (name "USB_DP") (class "Default")
      (node (ref "J2") (pin "5") (pinfunction "5_5") (pintype "passive"))
      (node (ref "R12") (pin "2") (pinfunction "2_2") (pintype "passive"))
      (node (ref "R5") (pin "1") (pinfunction "1_1") (pintype "passive"))
      (node (ref "U2") (pin "45") (pinfunction "PA12_45") (pintype "bidirectional"))
    )
    (net (code "77") (name "USB_P") (class "Default")
      (node (ref "R10") (pin "1") (pinfunction "1_1") (pintype "passive"))
      (node (ref "R11") (pin "2") (pinfunction "2_2") (pintype "passive"))
      (node (ref "U2") (pin "24") (pinfunction "PC4_24") (pintype "bidirectional"))
    )
    (net (code "78") (name "VANALOG") (class "Default")
      (node (ref "C11") (pin "1") (pinfunction "1_1") (pintype "passive"))
      (node (ref "C12") (pin "1") (pinfunction "1_1") (pintype "passive"))
      (node (ref "L3") (pin "2") (pinfunction "2_2") (pintype "passive"))
      (node (ref "U2") (pin "13") (pinfunction "VDDA_13") (pintype "bidirectional"))
    )
    (net (code "79") (name "VBAT") (class "Default")
      (node (ref "R16") (pin "1") (pinfunction "1_1") (pintype "passive"))
      (node (ref "R17") (pin "1") (pinfunction "1_1") (pintype "passive"))
      (node (ref "U2") (pin "1") (pinfunction "VBAT_1") (pintype "bidirectional"))
    )
    (net (code "80") (name "VBATIN") (class "Default")
      (node (ref "J2") (pin "1") (pinfunction "1_1") (pintype "passive"))
      (node (ref "R17") (pin "2") (pinfunction "2_2") (pintype "passive"))
    )
    (net (code "81") (name "WIFI_EN") (class "Default")
      (node (ref "U1") (pin "P26") (pinfunction "VBAT_SW_EN_P26") (pintype "bidirectional"))
    )
    (net (code "82") (name "unconnected-(U$7-NC-Pad4)") (class "Default")
      (node (ref "U$7") (pin "4") (pinfunction "NC_4") (pintype "bidirectional"))
    )
    (net (code "83") (name "unconnected-(U1-NC-PadP3)") (class "Default")
      (node (ref "U1") (pin "P3") (pinfunction "NC_P3") (pintype "bidirectional"))
    )
    (net (code "84") (name "unconnected-(U1-RESERVED_1-PadP2)") (class "Default")
      (node (ref "U1") (pin "P2") (pinfunction "RESERVED_1_P2") (pintype "bidirectional"))
    )
    (net (code "85") (name "unconnected-(U1-RESERVED_2-PadP4)") (class "Default")
      (node (ref "U1") (pin "P4") (pinfunction "RESERVED_2_P4") (pintype "bidirectional"))
    )
    (net (code "86") (name "unconnected-(U1-RESERVED_3-PadP24)") (class "Default")
      (node (ref "U1") (pin "P24") (pinfunction "RESERVED_3_P24") (pintype "bidirectional"))
    )
    (net (code "87") (name "unconnected-(U1-WL_RS232_RX-PadP8)") (class "Default")
      (node (ref "U1") (pin "P8") (pinfunction "WL_RS232_RX_P8") (pintype "bidirectional"))
    )
    (net (code "88") (name "unconnected-(U1-WL_RS232_TX-PadP6)") (class "Default")
      (node (ref "U1") (pin "P6") (pinfunction "WL_RS232_TX_P6") (pintype "bidirectional"))
    )
    (net (code "89") (name "unconnected-(U2-PB14-Pad35)") (class "Default")
      (node (ref "U2") (pin "35") (pinfunction "PB14_35") (pintype "bidirectional"))
    )
    (net (code "90") (name "unconnected-(U2-PB15-Pad36)") (class "Default")
      (node (ref "U2") (pin "36") (pinfunction "PB15_36") (pintype "bidirectional"))
    )
    (net (code "91") (name "unconnected-(U2-PC5-Pad25)") (class "Default")
      (node (ref "U2") (pin "25") (pinfunction "PC5_25") (pintype "bidirectional"))
    )
    (net (code "92") (name "unconnected-(U3-NC1-PadP9)") (class "Default")
      (node (ref "U3") (pin "P9") (pinfunction "NC1_P9") (pintype "bidirectional"))
    )
    (net (code "93") (name "unconnected-(U3-NC2-PadP10)") (class "Default")
      (node (ref "U3") (pin "P10") (pinfunction "NC2_P10") (pintype "bidirectional"))
    )
    (net (code "94") (name "unconnected-(U4-NC1-PadP2)") (class "Default")
      (node (ref "U4") (pin "P2") (pinfunction "NC1_P2") (pintype "bidirectional"))
    )
    (net (code "95") (name "unconnected-(U4-NC2-PadP5)") (class "Default")
      (node (ref "U4") (pin "P5") (pinfunction "NC2_P5") (pintype "bidirectional"))
    )
    (net (code "96") (name "unconnected-(U4-NC3-PadP6)") (class "Default")
      (node (ref "U4") (pin "P6") (pinfunction "NC3_P6") (pintype "bidirectional"))
    )
    (net (code "97") (name "unconnected-(U4-NC4-PadP7)") (class "Default")
      (node (ref "U4") (pin "P7") (pinfunction "NC4_P7") (pintype "bidirectional"))
    )
    (net (code "98") (name "unconnected-(U4-NC5-PadP12)") (class "Default")
      (node (ref "U4") (pin "P12") (pinfunction "NC5_P12") (pintype "bidirectional"))
    )
    (net (code "99") (name "unconnected-(U4-NC6-PadP13)") (class "Default")
      (node (ref "U4") (pin "P13") (pinfunction "NC6_P13") (pintype "bidirectional"))
    )
    (net (code "100") (name "unconnected-(U4-NC7-PadP14)") (class "Default")
      (node (ref "U4") (pin "P14") (pinfunction "NC7_P14") (pintype "bidirectional"))
    )
    (net (code "101") (name "unconnected-(U4-NC8-PadP16)") (class "Default")
      (node (ref "U4") (pin "P16") (pinfunction "NC8_P16") (pintype "bidirectional"))
    )
    (net (code "102") (name "unconnected-(U4-NC9-PadP17)") (class "Default")
      (node (ref "U4") (pin "P17") (pinfunction "NC9_P17") (pintype "bidirectional"))
    )
    (net (code "103") (name "unconnected-(U4-NC10-PadP18)") (class "Default")
      (node (ref "U4") (pin "P18") (pinfunction "NC10_P18") (pintype "bidirectional"))
    )
    (net (code "104") (name "unconnected-(U4-NC11-PadP20)") (class "Default")
      (node (ref "U4") (pin "P20") (pinfunction "NC11_P20") (pintype "bidirectional"))
    )
    (net (code "105") (name "unconnected-(U4-NC12-PadP21)") (class "Default")
      (node (ref "U4") (pin "P21") (pinfunction "NC12_P21") (pintype "bidirectional"))
    )
    (net (code "106") (name "unconnected-(U4-NC13-PadP22)") (class "Default")
      (node (ref "U4") (pin "P22") (pinfunction "NC13_P22") (pintype "bidirectional"))
    )
    (net (code "107") (name "unconnected-(U4-NC14-PadP23)") (class "Default")
      (node (ref "U4") (pin "P23") (pinfunction "NC14_P23") (pintype "bidirectional"))
    )
    (net (code "108") (name "unconnected-(U4-NC15-PadP24)") (class "Default")
      (node (ref "U4") (pin "P24") (pinfunction "NC15_P24") (pintype "bidirectional"))
    )
  )
)
